# conn_isouart.net
KiCad netlist of a schematic drawn in Altium Designer
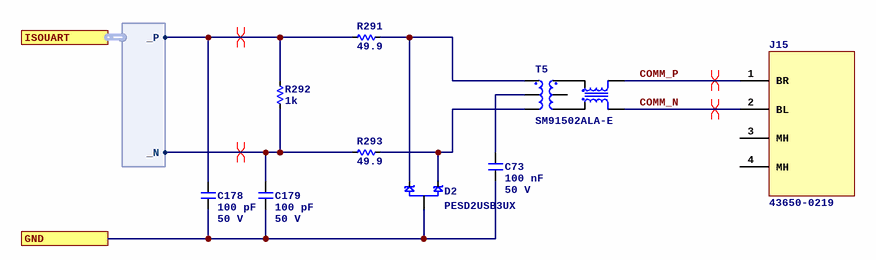
[diagram p0: conn_isouart.SchDoc]

(export (version "E")
  (design (tool "Eeschema 10.0.6"))
  (components
    (comp (ref "C73")
      (value "CL05B104KB54PNC")
      (footprint "C0402")
      (fields
        (field (name "CAPACITANCE") "100 nF")
        (field (name "MANUFACTURER") "Samsung Electro-Mechanics")
        (field (name "VOLTAGE RATING") "50 V")
      )
      (libsource (lib "database") (part "__template_cap"))
    )
    (comp (ref "C178")
      (value "CC0402KRX7R9BB101")
      (footprint "C0402")
      (fields
        (field (name "CAPACITANCE") "100 pF")
        (field (name "MANUFACTURER") "YAGEO")
        (field (name "VOLTAGE RATING") "50 V")
      )
      (libsource (lib "database") (part "__template_cap"))
    )
    (comp (ref "C179")
      (value "CC0402KRX7R9BB101")
      (footprint "C0402")
      (fields
        (field (name "CAPACITANCE") "100 pF")
        (field (name "MANUFACTURER") "YAGEO")
        (field (name "VOLTAGE RATING") "50 V")
      )
      (libsource (lib "database") (part "__template_cap"))
    )
    (comp (ref "D2")
      (value "PESD2USB3UX")
      (footprint "3SOT23")
      (description "DIODE ESD USB SOT-23")
      (fields (field (name "MANUFACTURER") "Nexperia USA Inc."))
      (libsource (lib "database") (part "PESD2USB3UX"))
    )
    (comp (ref "J15")
      (value "43650-0219")
      (footprint "MOLEX_MICROFIT_0436500219")
      (description "Connector Header Through Hole 2 position 0.118\" (3.00mm)")
      (fields (field (name "MANUFACTURER") "Molex"))
      (libsource (lib "database") (part "43650-0219"))
    )
    (comp (ref "R291")
      (value "49.9")
      (footprint "R0402")
      (fields
        (field (name "MANUFACTURER PART NUMBER") "0402WGF499JTCE")
        (field (name "MANUFACTURER") "UNI-ROYAL(Uniroyal Elec)")
        (field (name "TOLERANCE") "1%")
      )
      (libsource (lib "database") (part "__template_resistor"))
    )
    (comp (ref "R292")
      (value "1k")
      (footprint "R0402")
      (fields
        (field (name "MANUFACTURER PART NUMBER") "0402WGF1001TCE")
        (field (name "MANUFACTURER") "UNI-ROYAL(Uniroyal Elec)")
        (field (name "TOLERANCE") "1%")
      )
      (libsource (lib "database") (part "__template_resistor"))
    )
    (comp (ref "R293")
      (value "49.9")
      (footprint "R0402")
      (fields
        (field (name "MANUFACTURER PART NUMBER") "0402WGF499JTCE")
        (field (name "MANUFACTURER") "UNI-ROYAL(Uniroyal Elec)")
        (field (name "TOLERANCE") "1%")
      )
      (libsource (lib "database") (part "__template_resistor"))
    )
    (comp (ref "T5")
      (value "SM91502ALA-E")
      (footprint "BOURNS_SM91502")
      (description "200µH LAN Pulse Transformer 1CT:1CT Surface Mount")
      (fields (field (name "MANUFACTURER") "Bourns Inc."))
      (libsource (lib "database") (part "SM91502ALA-E"))
    )
  )
  (nets
    (net (code "2") (name "/COMM_N") (class "Default")
      (node (ref "J15") (pin "2") (pinfunction "BL_2") (pintype "passive"))
      (node (ref "T5") (pin "4") (pinfunction "4_4") (pintype "passive"))
    )
    (net (code "3") (name "/COMM_P") (class "Default")
      (node (ref "J15") (pin "1") (pinfunction "BR_1") (pintype "passive"))
      (node (ref "T5") (pin "6") (pinfunction "6_6") (pintype "passive"))
    )
    (net (code "4") (name "/GND") (class "Default")
      (node (ref "C178") (pin "2") (pintype "passive"))
      (node (ref "C179") (pin "2") (pintype "passive"))
      (node (ref "C73") (pin "2") (pintype "passive"))
      (node (ref "D2") (pin "3") (pintype "passive"))
    )
    (net (code "6") (name "Net-(C73-Pad1)") (class "Default")
      (node (ref "C73") (pin "1") (pintype "passive"))
      (node (ref "T5") (pin "2") (pinfunction "2_2") (pintype "passive"))
    )
    (net (code "7") (name "Net-(C178-Pad1)") (class "Default")
      (node (ref "C178") (pin "1") (pintype "passive"))
      (node (ref "R291") (pin "1") (pintype "passive"))
      (node (ref "R292") (pin "2") (pintype "passive"))
    )
    (net (code "8") (name "Net-(C179-Pad1)") (class "Default")
      (node (ref "C179") (pin "1") (pintype "passive"))
      (node (ref "R292") (pin "1") (pintype "passive"))
      (node (ref "R293") (pin "1") (pintype "passive"))
    )
    (net (code "9") (name "Net-(D2-Pad1)") (class "Default")
      (node (ref "D2") (pin "1") (pintype "passive"))
      (node (ref "R293") (pin "2") (pintype "passive"))
      (node (ref "T5") (pin "3") (pinfunction "3_3") (pintype "passive"))
    )
    (net (code "10") (name "Net-(D2-Pad2)") (class "Default")
      (node (ref "D2") (pin "2") (pintype "passive"))
      (node (ref "R291") (pin "2") (pintype "passive"))
      (node (ref "T5") (pin "1") (pinfunction "1_1") (pintype "passive"))
    )
    (net (code "11") (name "unconnected-(J15-MH-Pad3)") (class "Default")
      (node (ref "J15") (pin "3") (pinfunction "MH_3") (pintype "passive"))
    )
    (net (code "12") (name "unconnected-(J15-MH-Pad4)") (class "Default")
      (node (ref "J15") (pin "4") (pinfunction "MH_4") (pintype "passive"))
    )
    (net (code "13") (name "unconnected-(T5-Pad5)") (class "Default")
      (node (ref "T5") (pin "5") (pinfunction "5_5") (pintype "passive"))
    )
  )
)
